# ESP_HOME_ligh.net
KiCad netlist of a schematic drawn in EAGLE
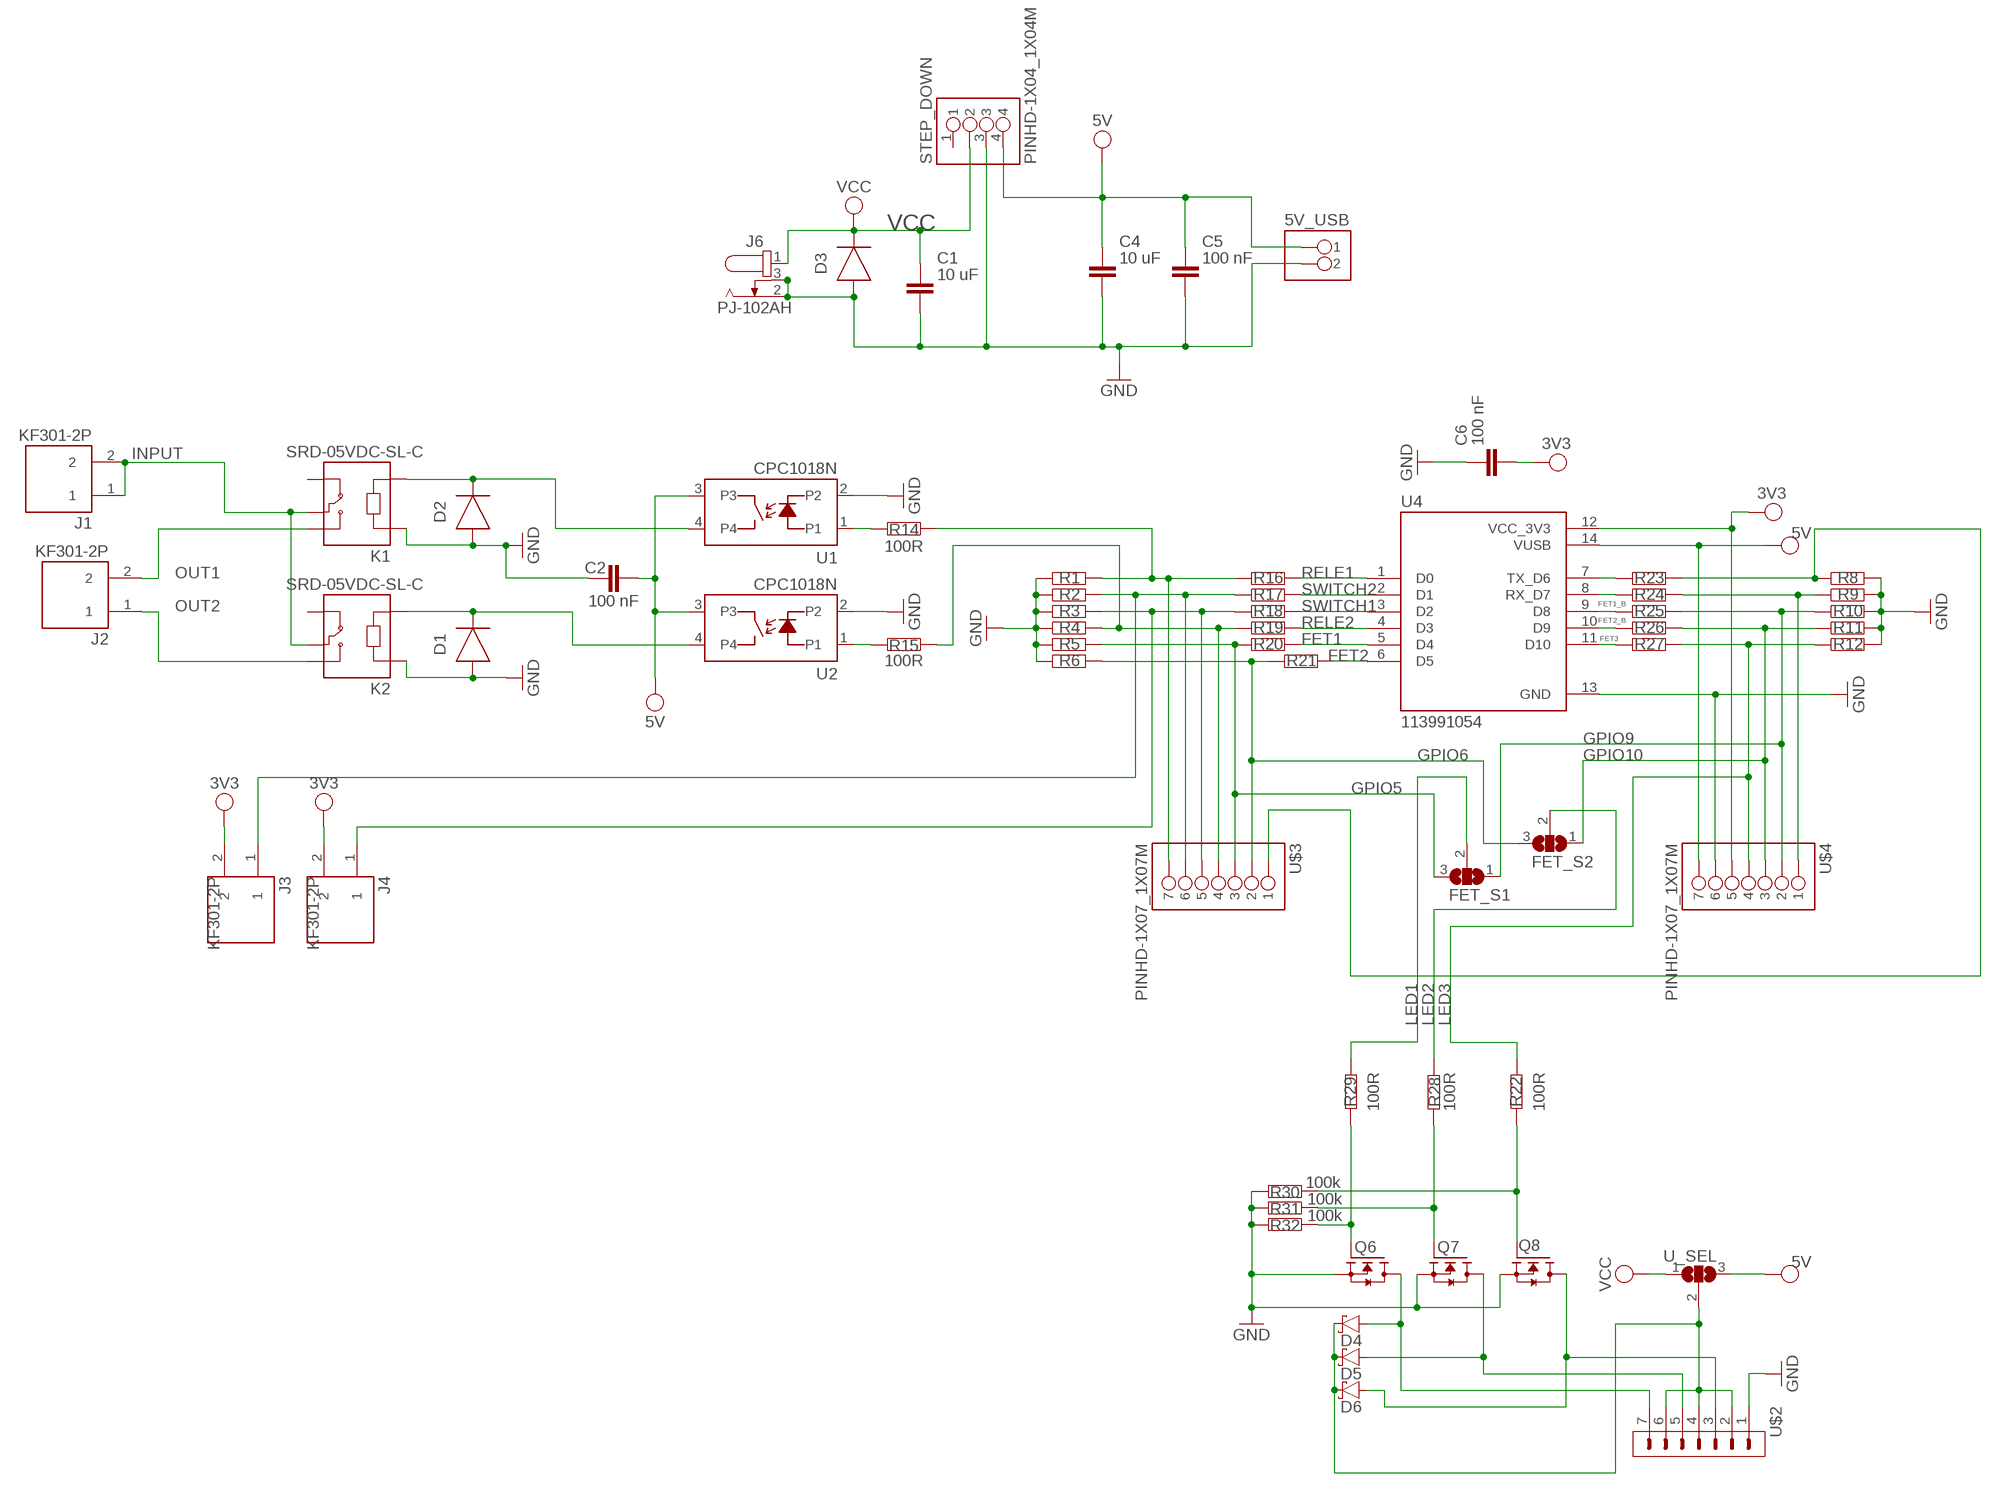
[diagram p0: schematic, sheet 1]

(export (version "E")
  (design (tool "Eeschema 10.0.6"))
  (components
    (comp (ref "5V_USB")
      (value "PINHD-1X02_1X02M")
      (footprint "eagle-import:1X02")
      (libsource (lib "eagle-import") (part "PINHD-1X02_1X02M"))
    )
    (comp (ref "C1")
      (value "10 uF")
      (footprint "eagle-import:CAPC2012X110")
      (libsource (lib "eagle-import") (part "CCHIP-0805(2012-METRIC)_"))
    )
    (comp (ref "C2")
      (value "100 nF")
      (footprint "eagle-import:CAPC2012X110")
      (libsource (lib "eagle-import") (part "CCHIP-0805(2012-METRIC)_"))
    )
    (comp (ref "C4")
      (value "10 uF")
      (footprint "eagle-import:CAPC2012X110")
      (libsource (lib "eagle-import") (part "CCHIP-0805(2012-METRIC)_"))
    )
    (comp (ref "C5")
      (value "100 nF")
      (footprint "eagle-import:CAPC2012X110")
      (libsource (lib "eagle-import") (part "CCHIP-0805(2012-METRIC)_"))
    )
    (comp (ref "C6")
      (value "100 nF")
      (footprint "eagle-import:CAPC2012X110")
      (libsource (lib "eagle-import") (part "CCHIP-0805(2012-METRIC)_"))
    )
    (comp (ref "D1")
      (value "DIODEDIODE-AXIAL")
      (footprint "eagle-import:DIODE-AXIAL")
      (libsource (lib "eagle-import") (part "DIODEDIODE-AXIAL"))
    )
    (comp (ref "D2")
      (value "DIODEDIODE-AXIAL")
      (footprint "eagle-import:DIODE-AXIAL")
      (libsource (lib "eagle-import") (part "DIODEDIODE-AXIAL"))
    )
    (comp (ref "D3")
      (value "DIODEDIODE-AXIAL")
      (footprint "eagle-import:DIODE-AXIAL")
      (libsource (lib "eagle-import") (part "DIODEDIODE-AXIAL"))
    )
    (comp (ref "D4")
      (value "SCHOTTKY_MBR0520LT1GDO-219")
      (footprint "eagle-import:SODFL3718X115")
      (fields (field (name "MANUFACTURER") "onsemi") (field (name "MPN") "MBR0520LT1G"))
      (libsource (lib "eagle-import") (part "SCHOTTKY_DO-219MBR0520LT1G"))
    )
    (comp (ref "D5")
      (value "SCHOTTKY_MBR0520LT1GDO-219")
      (footprint "eagle-import:SODFL3718X115")
      (fields (field (name "MANUFACTURER") "onsemi") (field (name "MPN") "MBR0520LT1G"))
      (libsource (lib "eagle-import") (part "SCHOTTKY_DO-219MBR0520LT1G"))
    )
    (comp (ref "D6")
      (value "SCHOTTKY_MBR0520LT1GDO-219")
      (footprint "eagle-import:SODFL3718X115")
      (fields (field (name "MANUFACTURER") "onsemi") (field (name "MPN") "MBR0520LT1G"))
      (libsource (lib "eagle-import") (part "SCHOTTKY_DO-219MBR0520LT1G"))
    )
    (comp (ref "FET_S1")
      (value "SJ2W")
      (footprint "eagle-import:SJ_2")
      (libsource (lib "eagle-import") (part "SJ2W"))
    )
    (comp (ref "FET_S2")
      (value "SJ2W")
      (footprint "eagle-import:SJ_2")
      (libsource (lib "eagle-import") (part "SJ2W"))
    )
    (comp (ref "J1")
      (value "KF301-2P")
      (footprint "eagle-import:HANDSON_KF301-2P")
      (fields (field (name "MF") "Handson Technology"))
      (libsource (lib "eagle-import") (part "KF301-2P"))
    )
    (comp (ref "J2")
      (value "KF301-2P")
      (footprint "eagle-import:HANDSON_KF301-2P")
      (fields (field (name "MF") "Handson Technology"))
      (libsource (lib "eagle-import") (part "KF301-2P"))
    )
    (comp (ref "J3")
      (value "KF301-2P")
      (footprint "eagle-import:HANDSON_KF301-2P")
      (fields (field (name "MF") "Handson Technology"))
      (libsource (lib "eagle-import") (part "KF301-2P"))
    )
    (comp (ref "J4")
      (value "KF301-2P")
      (footprint "eagle-import:HANDSON_KF301-2P")
      (fields (field (name "MF") "Handson Technology"))
      (libsource (lib "eagle-import") (part "KF301-2P"))
    )
    (comp (ref "J6")
      (value "PJ-102AH")
      (footprint "eagle-import:PJ-102AH")
      (fields (field (name "MANUFACTURER") "Same Sky"))
      (libsource (lib "eagle-import") (part "PJ-102AH"))
    )
    (comp (ref "K1")
      (value "SRD-05VDC-SL-C")
      (footprint "eagle-import:RELAY_SRD-05VDC-SL-C")
      (fields (field (name "MF") "Songle Relay"))
      (libsource (lib "eagle-import") (part "SRD-05VDC-SL-C"))
    )
    (comp (ref "K2")
      (value "SRD-05VDC-SL-C")
      (footprint "eagle-import:RELAY_SRD-05VDC-SL-C")
      (fields (field (name "MF") "Songle Relay"))
      (libsource (lib "eagle-import") (part "SRD-05VDC-SL-C"))
    )
    (comp (ref "Q6")
      (value "AO3400A")
      (footprint "eagle-import:SOT95P280X125-3N")
      (fields (field (name "MF") "Alpha & Omega Semiconductor"))
      (libsource (lib "eagle-import") (part "AO3400A"))
    )
    (comp (ref "Q7")
      (value "AO3400A")
      (footprint "eagle-import:SOT95P280X125-3N")
      (fields (field (name "MF") "Alpha & Omega Semiconductor"))
      (libsource (lib "eagle-import") (part "AO3400A"))
    )
    (comp (ref "Q8")
      (value "AO3400A")
      (footprint "eagle-import:SOT95P280X125-3N")
      (fields (field (name "MF") "Alpha & Omega Semiconductor"))
      (libsource (lib "eagle-import") (part "AO3400A"))
    )
    (comp (ref "R1")
      (value "R_CHIP-1206(3216-METRIC)")
      (footprint "eagle-import:RESC3216X70")
      (libsource (lib "eagle-import") (part "RCHIP-1206(3216-METRIC)_"))
    )
    (comp (ref "R2")
      (value "R_CHIP-1206(3216-METRIC)")
      (footprint "eagle-import:RESC3216X70")
      (libsource (lib "eagle-import") (part "RCHIP-1206(3216-METRIC)_"))
    )
    (comp (ref "R3")
      (value "R_CHIP-1206(3216-METRIC)")
      (footprint "eagle-import:RESC3216X70")
      (libsource (lib "eagle-import") (part "RCHIP-1206(3216-METRIC)_"))
    )
    (comp (ref "R4")
      (value "R_CHIP-1206(3216-METRIC)")
      (footprint "eagle-import:RESC3216X70")
      (libsource (lib "eagle-import") (part "RCHIP-1206(3216-METRIC)_"))
    )
    (comp (ref "R5")
      (value "R_CHIP-1206(3216-METRIC)")
      (footprint "eagle-import:RESC3216X70")
      (libsource (lib "eagle-import") (part "RCHIP-1206(3216-METRIC)_"))
    )
    (comp (ref "R6")
      (value "R_CHIP-1206(3216-METRIC)")
      (footprint "eagle-import:RESC3216X70")
      (libsource (lib "eagle-import") (part "RCHIP-1206(3216-METRIC)_"))
    )
    (comp (ref "R8")
      (value "R_CHIP-1206(3216-METRIC)")
      (footprint "eagle-import:RESC3216X70")
      (libsource (lib "eagle-import") (part "RCHIP-1206(3216-METRIC)_"))
    )
    (comp (ref "R9")
      (value "R_CHIP-1206(3216-METRIC)")
      (footprint "eagle-import:RESC3216X70")
      (libsource (lib "eagle-import") (part "RCHIP-1206(3216-METRIC)_"))
    )
    (comp (ref "R10")
      (value "R_CHIP-1206(3216-METRIC)")
      (footprint "eagle-import:RESC3216X70")
      (libsource (lib "eagle-import") (part "RCHIP-1206(3216-METRIC)_"))
    )
    (comp (ref "R11")
      (value "R_CHIP-1206(3216-METRIC)")
      (footprint "eagle-import:RESC3216X70")
      (libsource (lib "eagle-import") (part "RCHIP-1206(3216-METRIC)_"))
    )
    (comp (ref "R12")
      (value "R_CHIP-1206(3216-METRIC)")
      (footprint "eagle-import:RESC3216X70")
      (libsource (lib "eagle-import") (part "RCHIP-1206(3216-METRIC)_"))
    )
    (comp (ref "R14")
      (value "100R")
      (footprint "eagle-import:RESC3216X70")
      (libsource (lib "eagle-import") (part "RCHIP-1206(3216-METRIC)_"))
    )
    (comp (ref "R15")
      (value "100R")
      (footprint "eagle-import:RESC3216X70")
      (libsource (lib "eagle-import") (part "RCHIP-1206(3216-METRIC)_"))
    )
    (comp (ref "R16")
      (value "R_CHIP-1206(3216-METRIC)")
      (footprint "eagle-import:RESC3216X70")
      (libsource (lib "eagle-import") (part "RCHIP-1206(3216-METRIC)_"))
    )
    (comp (ref "R17")
      (value "R_CHIP-1206(3216-METRIC)")
      (footprint "eagle-import:RESC3216X70")
      (libsource (lib "eagle-import") (part "RCHIP-1206(3216-METRIC)_"))
    )
    (comp (ref "R18")
      (value "R_CHIP-1206(3216-METRIC)")
      (footprint "eagle-import:RESC3216X70")
      (libsource (lib "eagle-import") (part "RCHIP-1206(3216-METRIC)_"))
    )
    (comp (ref "R19")
      (value "R_CHIP-1206(3216-METRIC)")
      (footprint "eagle-import:RESC3216X70")
      (libsource (lib "eagle-import") (part "RCHIP-1206(3216-METRIC)_"))
    )
    (comp (ref "R20")
      (value "R_CHIP-1206(3216-METRIC)")
      (footprint "eagle-import:RESC3216X70")
      (libsource (lib "eagle-import") (part "RCHIP-1206(3216-METRIC)_"))
    )
    (comp (ref "R21")
      (value "R_CHIP-1206(3216-METRIC)")
      (footprint "eagle-import:RESC3216X70")
      (libsource (lib "eagle-import") (part "RCHIP-1206(3216-METRIC)_"))
    )
    (comp (ref "R22")
      (value "100R")
      (footprint "eagle-import:RESC3216X70")
      (libsource (lib "eagle-import") (part "RCHIP-1206(3216-METRIC)_"))
    )
    (comp (ref "R23")
      (value "R_CHIP-1206(3216-METRIC)")
      (footprint "eagle-import:RESC3216X70")
      (libsource (lib "eagle-import") (part "RCHIP-1206(3216-METRIC)_"))
    )
    (comp (ref "R24")
      (value "R_CHIP-1206(3216-METRIC)")
      (footprint "eagle-import:RESC3216X70")
      (libsource (lib "eagle-import") (part "RCHIP-1206(3216-METRIC)_"))
    )
    (comp (ref "R25")
      (value "R_CHIP-1206(3216-METRIC)")
      (footprint "eagle-import:RESC3216X70")
      (libsource (lib "eagle-import") (part "RCHIP-1206(3216-METRIC)_"))
    )
    (comp (ref "R26")
      (value "R_CHIP-1206(3216-METRIC)")
      (footprint "eagle-import:RESC3216X70")
      (libsource (lib "eagle-import") (part "RCHIP-1206(3216-METRIC)_"))
    )
    (comp (ref "R27")
      (value "R_CHIP-1206(3216-METRIC)")
      (footprint "eagle-import:RESC3216X70")
      (libsource (lib "eagle-import") (part "RCHIP-1206(3216-METRIC)_"))
    )
    (comp (ref "R28")
      (value "100R")
      (footprint "eagle-import:RESC3216X70")
      (libsource (lib "eagle-import") (part "RCHIP-1206(3216-METRIC)_"))
    )
    (comp (ref "R29")
      (value "100R")
      (footprint "eagle-import:RESC3216X70")
      (libsource (lib "eagle-import") (part "RCHIP-1206(3216-METRIC)_"))
    )
    (comp (ref "R30")
      (value "100k")
      (footprint "eagle-import:RESC3216X70")
      (libsource (lib "eagle-import") (part "RCHIP-1206(3216-METRIC)_"))
    )
    (comp (ref "R31")
      (value "100k")
      (footprint "eagle-import:RESC3216X70")
      (libsource (lib "eagle-import") (part "RCHIP-1206(3216-METRIC)_"))
    )
    (comp (ref "R32")
      (value "100k")
      (footprint "eagle-import:RESC3216X70")
      (libsource (lib "eagle-import") (part "RCHIP-1206(3216-METRIC)_"))
    )
    (comp (ref "STEP_DOWN")
      (value "PINHD-1X04_1X04M")
      (footprint "eagle-import:1X04")
      (libsource (lib "eagle-import") (part "PINHD-1X04_1X04M"))
    )
    (comp (ref "U$2")
      (value "PINHD-1X7")
      (footprint "eagle-import:1X07")
      (libsource (lib "eagle-import") (part "PINHD-1X7"))
    )
    (comp (ref "U$3")
      (value "PINHD-1X07_1X07M")
      (footprint "eagle-import:1X07")
      (libsource (lib "eagle-import") (part "PINHD-1X07_1X07M"))
    )
    (comp (ref "U$4")
      (value "PINHD-1X07_1X07M")
      (footprint "eagle-import:1X07")
      (libsource (lib "eagle-import") (part "PINHD-1X07_1X07M"))
    )
    (comp (ref "U1")
      (value "CPC1018N")
      (footprint "eagle-import:CLARE_SO4")
      (fields (field (name "MF") "IXYS Integrated Circuits"))
      (libsource (lib "eagle-import") (part "CPC1018N"))
    )
    (comp (ref "U2")
      (value "CPC1018N")
      (footprint "eagle-import:CLARE_SO4")
      (fields (field (name "MF") "IXYS Integrated Circuits"))
      (libsource (lib "eagle-import") (part "CPC1018N"))
    )
    (comp (ref "U4")
      (value "113991054")
      (footprint "eagle-import:MODULE_113991054")
      (fields (field (name "MF") "Seeed Technology Co., Ltd"))
      (libsource (lib "eagle-import") (part "113991054"))
    )
    (comp (ref "U_SEL")
      (value "SJ2W")
      (footprint "eagle-import:SJ_2")
      (libsource (lib "eagle-import") (part "SJ2W"))
    )
  )
  (nets
    (net (code "1") (name "/FET1") (class "Default")
      (node (ref "R20") (pin "2") (pinfunction "2_2") (pintype "passive"))
      (node (ref "U4") (pin "5") (pinfunction "D4_5") (pintype "bidirectional"))
    )
    (net (code "2") (name "/FET1_B") (class "Default")
      (node (ref "R25") (pin "1") (pinfunction "1_1") (pintype "passive"))
      (node (ref "U4") (pin "9") (pinfunction "D8_9") (pintype "bidirectional"))
    )
    (net (code "3") (name "/FET2") (class "Default")
      (node (ref "R21") (pin "2") (pinfunction "2_2") (pintype "passive"))
      (node (ref "U4") (pin "6") (pinfunction "D5_6") (pintype "bidirectional"))
    )
    (net (code "4") (name "/FET2_B") (class "Default")
      (node (ref "R26") (pin "1") (pinfunction "1_1") (pintype "passive"))
      (node (ref "U4") (pin "10") (pinfunction "D9_10") (pintype "bidirectional"))
    )
    (net (code "5") (name "/FET3") (class "Default")
      (node (ref "R27") (pin "1") (pinfunction "1_1") (pintype "passive"))
      (node (ref "U4") (pin "11") (pinfunction "D10_11") (pintype "bidirectional"))
    )
    (net (code "6") (name "/GPIO5") (class "Default")
      (node (ref "FET_S1") (pin "3") (pinfunction "3_3") (pintype "passive"))
      (node (ref "R20") (pin "1") (pinfunction "1_1") (pintype "passive"))
      (node (ref "R5") (pin "2") (pinfunction "2_2") (pintype "passive"))
      (node (ref "U$3") (pin "3") (pinfunction "3_3") (pintype "bidirectional"))
    )
    (net (code "7") (name "/GPIO6") (class "Default")
      (node (ref "FET_S2") (pin "3") (pinfunction "3_3") (pintype "passive"))
      (node (ref "R21") (pin "1") (pinfunction "1_1") (pintype "passive"))
      (node (ref "R6") (pin "2") (pinfunction "2_2") (pintype "passive"))
      (node (ref "U$3") (pin "2") (pinfunction "2_2") (pintype "bidirectional"))
    )
    (net (code "8") (name "/GPIO9") (class "Default")
      (node (ref "FET_S1") (pin "1") (pinfunction "1_1") (pintype "passive"))
      (node (ref "R10") (pin "1") (pinfunction "1_1") (pintype "passive"))
      (node (ref "R25") (pin "2") (pinfunction "2_2") (pintype "passive"))
      (node (ref "U$4") (pin "2") (pinfunction "2_2") (pintype "bidirectional"))
    )
    (net (code "9") (name "/GPIO10") (class "Default")
      (node (ref "FET_S2") (pin "1") (pinfunction "1_1") (pintype "passive"))
      (node (ref "R11") (pin "1") (pinfunction "1_1") (pintype "passive"))
      (node (ref "R26") (pin "2") (pinfunction "2_2") (pintype "passive"))
      (node (ref "U$4") (pin "3") (pinfunction "3_3") (pintype "bidirectional"))
    )
    (net (code "10") (name "/INPUT") (class "Default")
      (node (ref "J1") (pin "1") (pinfunction "1_1") (pintype "passive"))
      (node (ref "J1") (pin "2") (pinfunction "2_2") (pintype "passive"))
      (node (ref "K1") (pin "COM") (pinfunction "COM_COM") (pintype "passive"))
      (node (ref "K2") (pin "COM") (pinfunction "COM_COM") (pintype "passive"))
    )
    (net (code "11") (name "/LED1") (class "Default")
      (node (ref "FET_S1") (pin "2") (pinfunction "2_2") (pintype "passive"))
      (node (ref "R29") (pin "2") (pinfunction "2_2") (pintype "passive"))
    )
    (net (code "12") (name "/LED2") (class "Default")
      (node (ref "FET_S2") (pin "2") (pinfunction "2_2") (pintype "passive"))
      (node (ref "R28") (pin "1") (pinfunction "1_1") (pintype "passive"))
    )
    (net (code "13") (name "/LED3") (class "Default")
      (node (ref "R12") (pin "1") (pinfunction "1_1") (pintype "passive"))
      (node (ref "R22") (pin "2") (pinfunction "2_2") (pintype "passive"))
      (node (ref "R27") (pin "2") (pinfunction "2_2") (pintype "passive"))
      (node (ref "U$4") (pin "4") (pinfunction "4_4") (pintype "bidirectional"))
    )
    (net (code "14") (name "/OUT1") (class "Default")
      (node (ref "J2") (pin "2") (pinfunction "2_2") (pintype "passive"))
      (node (ref "K1") (pin "NO") (pinfunction "NO_NO") (pintype "passive"))
    )
    (net (code "15") (name "/OUT2") (class "Default")
      (node (ref "J2") (pin "1") (pinfunction "1_1") (pintype "passive"))
      (node (ref "K2") (pin "NO") (pinfunction "NO_NO") (pintype "passive"))
    )
    (net (code "16") (name "/RELE1") (class "Default")
      (node (ref "R16") (pin "2") (pinfunction "2_2") (pintype "passive"))
      (node (ref "U4") (pin "1") (pinfunction "D0_1") (pintype "bidirectional"))
    )
    (net (code "17") (name "/RELE2") (class "Default")
      (node (ref "R19") (pin "2") (pinfunction "2_2") (pintype "passive"))
      (node (ref "U4") (pin "4") (pinfunction "D3_4") (pintype "bidirectional"))
    )
    (net (code "18") (name "/SWITCH1") (class "Default")
      (node (ref "R18") (pin "2") (pinfunction "2_2") (pintype "passive"))
      (node (ref "U4") (pin "3") (pinfunction "D2_3") (pintype "bidirectional"))
    )
    (net (code "19") (name "/SWITCH2") (class "Default")
      (node (ref "R17") (pin "2") (pinfunction "2_2") (pintype "passive"))
      (node (ref "U4") (pin "2") (pinfunction "D1_2") (pintype "bidirectional"))
    )
    (net (code "20") (name "3V3") (class "Default")
      (node (ref "C6") (pin "2") (pinfunction "2_2") (pintype "passive"))
      (node (ref "J3") (pin "2") (pinfunction "2_2") (pintype "passive"))
      (node (ref "J4") (pin "2") (pinfunction "2_2") (pintype "passive"))
      (node (ref "U$4") (pin "5") (pinfunction "5_5") (pintype "bidirectional"))
      (node (ref "U4") (pin "12") (pinfunction "VCC_3V3_12") (pintype "power_in"))
    )
    (net (code "21") (name "5V") (class "Default")
      (node (ref "5V_USB") (pin "1") (pinfunction "1_1") (pintype "bidirectional"))
      (node (ref "C2") (pin "2") (pinfunction "2_2") (pintype "passive"))
      (node (ref "C4") (pin "1") (pinfunction "1_1") (pintype "passive"))
      (node (ref "C5") (pin "1") (pinfunction "1_1") (pintype "passive"))
      (node (ref "STEP_DOWN") (pin "4") (pinfunction "4_4") (pintype "bidirectional"))
      (node (ref "U$4") (pin "7") (pinfunction "7_7") (pintype "bidirectional"))
      (node (ref "U1") (pin "3") (pinfunction "P3_3") (pintype "passive"))
      (node (ref "U2") (pin "3") (pinfunction "P3_3") (pintype "passive"))
      (node (ref "U4") (pin "14") (pinfunction "VUSB_14") (pintype "power_in"))
      (node (ref "U_SEL") (pin "3") (pinfunction "3_3") (pintype "passive"))
    )
    (net (code "22") (name "GND") (class "Default")
      (node (ref "5V_USB") (pin "2") (pinfunction "2_2") (pintype "bidirectional"))
      (node (ref "C1") (pin "2") (pinfunction "2_2") (pintype "passive"))
      (node (ref "C2") (pin "1") (pinfunction "1_1") (pintype "passive"))
      (node (ref "C4") (pin "2") (pinfunction "2_2") (pintype "passive"))
      (node (ref "C5") (pin "2") (pinfunction "2_2") (pintype "passive"))
      (node (ref "C6") (pin "1") (pinfunction "1_1") (pintype "passive"))
      (node (ref "D1") (pin "1") (pinfunction "A_1") (pintype "passive"))
      (node (ref "D2") (pin "1") (pinfunction "A_1") (pintype "passive"))
      (node (ref "D3") (pin "1") (pinfunction "A_1") (pintype "passive"))
      (node (ref "J6") (pin "2") (pinfunction "2_2") (pintype "passive"))
      (node (ref "J6") (pin "3") (pinfunction "3_3") (pintype "passive"))
      (node (ref "K1") (pin "A1") (pinfunction "A1_A1") (pintype "passive"))
      (node (ref "K2") (pin "A1") (pinfunction "A1_A1") (pintype "passive"))
      (node (ref "Q6") (pin "2") (pinfunction "S_2") (pintype "passive"))
      (node (ref "Q7") (pin "2") (pinfunction "S_2") (pintype "passive"))
      (node (ref "Q8") (pin "2") (pinfunction "S_2") (pintype "passive"))
      (node (ref "R1") (pin "1") (pinfunction "1_1") (pintype "passive"))
      (node (ref "R10") (pin "2") (pinfunction "2_2") (pintype "passive"))
      (node (ref "R11") (pin "2") (pinfunction "2_2") (pintype "passive"))
      (node (ref "R12") (pin "2") (pinfunction "2_2") (pintype "passive"))
      (node (ref "R2") (pin "1") (pinfunction "1_1") (pintype "passive"))
      (node (ref "R3") (pin "1") (pinfunction "1_1") (pintype "passive"))
      (node (ref "R30") (pin "2") (pinfunction "2_2") (pintype "passive"))
      (node (ref "R31") (pin "2") (pinfunction "2_2") (pintype "passive"))
      (node (ref "R32") (pin "2") (pinfunction "2_2") (pintype "passive"))
      (node (ref "R4") (pin "1") (pinfunction "1_1") (pintype "passive"))
      (node (ref "R5") (pin "1") (pinfunction "1_1") (pintype "passive"))
      (node (ref "R6") (pin "1") (pinfunction "1_1") (pintype "passive"))
      (node (ref "R8") (pin "2") (pinfunction "2_2") (pintype "passive"))
      (node (ref "R9") (pin "2") (pinfunction "2_2") (pintype "passive"))
      (node (ref "STEP_DOWN") (pin "3") (pinfunction "3_3") (pintype "bidirectional"))
      (node (ref "U$2") (pin "1") (pinfunction "1_1") (pintype "passive"))
      (node (ref "U$4") (pin "6") (pinfunction "6_6") (pintype "bidirectional"))
      (node (ref "U1") (pin "2") (pinfunction "P2_2") (pintype "passive"))
      (node (ref "U2") (pin "2") (pinfunction "P2_2") (pintype "passive"))
      (node (ref "U4") (pin "13") (pinfunction "GND_13") (pintype "power_in"))
    )
    (net (code "23") (name "Net-(D1-C)") (class "Default")
      (node (ref "D1") (pin "2") (pinfunction "C_2") (pintype "passive"))
      (node (ref "K2") (pin "A2") (pinfunction "A2_A2") (pintype "passive"))
      (node (ref "U2") (pin "4") (pinfunction "P4_4") (pintype "passive"))
    )
    (net (code "24") (name "Net-(D2-C)") (class "Default")
      (node (ref "D2") (pin "2") (pinfunction "C_2") (pintype "passive"))
      (node (ref "K1") (pin "A2") (pinfunction "A2_A2") (pintype "passive"))
      (node (ref "U1") (pin "4") (pinfunction "P4_4") (pintype "passive"))
    )
    (net (code "25") (name "Net-(D4-A)") (class "Default")
      (node (ref "D4") (pin "2") (pinfunction "A_2") (pintype "passive"))
      (node (ref "Q6") (pin "3") (pinfunction "D_3") (pintype "passive"))
      (node (ref "U$2") (pin "7") (pinfunction "7_7") (pintype "passive"))
    )
    (net (code "26") (name "Net-(D4-C)") (class "Default")
      (node (ref "D4") (pin "1") (pinfunction "C_1") (pintype "passive"))
      (node (ref "D5") (pin "1") (pinfunction "C_1") (pintype "passive"))
      (node (ref "D6") (pin "1") (pinfunction "C_1") (pintype "passive"))
      (node (ref "U$2") (pin "2") (pinfunction "2_2") (pintype "passive"))
      (node (ref "U$2") (pin "4") (pinfunction "4_4") (pintype "passive"))
      (node (ref "U$2") (pin "6") (pinfunction "6_6") (pintype "passive"))
      (node (ref "U_SEL") (pin "2") (pinfunction "2_2") (pintype "passive"))
    )
    (net (code "27") (name "Net-(D5-A)") (class "Default")
      (node (ref "D5") (pin "2") (pinfunction "A_2") (pintype "passive"))
      (node (ref "Q7") (pin "3") (pinfunction "D_3") (pintype "passive"))
      (node (ref "U$2") (pin "5") (pinfunction "5_5") (pintype "passive"))
    )
    (net (code "28") (name "Net-(D6-A)") (class "Default")
      (node (ref "D6") (pin "2") (pinfunction "A_2") (pintype "passive"))
      (node (ref "Q8") (pin "3") (pinfunction "D_3") (pintype "passive"))
      (node (ref "U$2") (pin "3") (pinfunction "3_3") (pintype "passive"))
    )
    (net (code "29") (name "Net-(J3-Pad1)") (class "Default")
      (node (ref "J3") (pin "1") (pinfunction "1_1") (pintype "passive"))
      (node (ref "R17") (pin "1") (pinfunction "1_1") (pintype "passive"))
      (node (ref "R2") (pin "2") (pinfunction "2_2") (pintype "passive"))
      (node (ref "U$3") (pin "6") (pinfunction "6_6") (pintype "bidirectional"))
    )
    (net (code "30") (name "Net-(J4-Pad1)") (class "Default")
      (node (ref "J4") (pin "1") (pinfunction "1_1") (pintype "passive"))
      (node (ref "R18") (pin "1") (pinfunction "1_1") (pintype "passive"))
      (node (ref "R3") (pin "2") (pinfunction "2_2") (pintype "passive"))
      (node (ref "U$3") (pin "5") (pinfunction "5_5") (pintype "bidirectional"))
    )
    (net (code "31") (name "Net-(Q6-G)") (class "Default")
      (node (ref "Q6") (pin "1") (pinfunction "G_1") (pintype "passive"))
      (node (ref "R29") (pin "1") (pinfunction "1_1") (pintype "passive"))
      (node (ref "R32") (pin "1") (pinfunction "1_1") (pintype "passive"))
    )
    (net (code "32") (name "Net-(Q7-G)") (class "Default")
      (node (ref "Q7") (pin "1") (pinfunction "G_1") (pintype "passive"))
      (node (ref "R28") (pin "2") (pinfunction "2_2") (pintype "passive"))
      (node (ref "R31") (pin "1") (pinfunction "1_1") (pintype "passive"))
    )
    (net (code "33") (name "Net-(Q8-G)") (class "Default")
      (node (ref "Q8") (pin "1") (pinfunction "G_1") (pintype "passive"))
      (node (ref "R22") (pin "1") (pinfunction "1_1") (pintype "passive"))
      (node (ref "R30") (pin "1") (pinfunction "1_1") (pintype "passive"))
    )
    (net (code "34") (name "Net-(R1-Pad2)") (class "Default")
      (node (ref "R1") (pin "2") (pinfunction "2_2") (pintype "passive"))
      (node (ref "R14") (pin "1") (pinfunction "1_1") (pintype "passive"))
      (node (ref "R16") (pin "1") (pinfunction "1_1") (pintype "passive"))
      (node (ref "U$3") (pin "7") (pinfunction "7_7") (pintype "bidirectional"))
    )
    (net (code "35") (name "Net-(R15-Pad1)") (class "Default")
      (node (ref "R15") (pin "1") (pinfunction "1_1") (pintype "passive"))
      (node (ref "R19") (pin "1") (pinfunction "1_1") (pintype "passive"))
      (node (ref "R4") (pin "2") (pinfunction "2_2") (pintype "passive"))
      (node (ref "U$3") (pin "4") (pinfunction "4_4") (pintype "bidirectional"))
    )
    (net (code "36") (name "Net-(R23-Pad2)") (class "Default")
      (node (ref "R23") (pin "2") (pinfunction "2_2") (pintype "passive"))
      (node (ref "R8") (pin "1") (pinfunction "1_1") (pintype "passive"))
      (node (ref "U$3") (pin "1") (pinfunction "1_1") (pintype "bidirectional"))
    )
    (net (code "37") (name "Net-(R24-Pad2)") (class "Default")
      (node (ref "R24") (pin "2") (pinfunction "2_2") (pintype "passive"))
      (node (ref "R9") (pin "1") (pinfunction "1_1") (pintype "passive"))
      (node (ref "U$4") (pin "1") (pinfunction "1_1") (pintype "bidirectional"))
    )
    (net (code "38") (name "Net-(U1-P1)") (class "Default")
      (node (ref "R14") (pin "2") (pinfunction "2_2") (pintype "passive"))
      (node (ref "U1") (pin "1") (pinfunction "P1_1") (pintype "passive"))
    )
    (net (code "39") (name "Net-(U2-P1)") (class "Default")
      (node (ref "R15") (pin "2") (pinfunction "2_2") (pintype "passive"))
      (node (ref "U2") (pin "1") (pinfunction "P1_1") (pintype "passive"))
    )
    (net (code "40") (name "Net-(U4-RX_D7)") (class "Default")
      (node (ref "R24") (pin "1") (pinfunction "1_1") (pintype "passive"))
      (node (ref "U4") (pin "8") (pinfunction "RX_D7_8") (pintype "bidirectional"))
    )
    (net (code "41") (name "Net-(U4-TX_D6)") (class "Default")
      (node (ref "R23") (pin "1") (pinfunction "1_1") (pintype "passive"))
      (node (ref "U4") (pin "7") (pinfunction "TX_D6_7") (pintype "bidirectional"))
    )
    (net (code "42") (name "VCC") (class "Default")
      (node (ref "C1") (pin "1") (pinfunction "1_1") (pintype "passive"))
      (node (ref "D3") (pin "2") (pinfunction "C_2") (pintype "passive"))
      (node (ref "J6") (pin "1") (pinfunction "1_1") (pintype "passive"))
      (node (ref "STEP_DOWN") (pin "2") (pinfunction "2_2") (pintype "bidirectional"))
      (node (ref "U_SEL") (pin "1") (pinfunction "1_1") (pintype "passive"))
    )
    (net (code "43") (name "unconnected-(K1-PadNC)") (class "Default")
      (node (ref "K1") (pin "NC") (pinfunction "NC_NC") (pintype "passive"))
    )
    (net (code "44") (name "unconnected-(K2-PadNC)") (class "Default")
      (node (ref "K2") (pin "NC") (pinfunction "NC_NC") (pintype "passive"))
    )
    (net (code "45") (name "unconnected-(STEP_DOWN-Pad1)") (class "Default")
      (node (ref "STEP_DOWN") (pin "1") (pinfunction "1_1") (pintype "bidirectional"))
    )
  )
)
